# child_altium-designer.net
KiCad netlist of a schematic drawn in Altium Designer
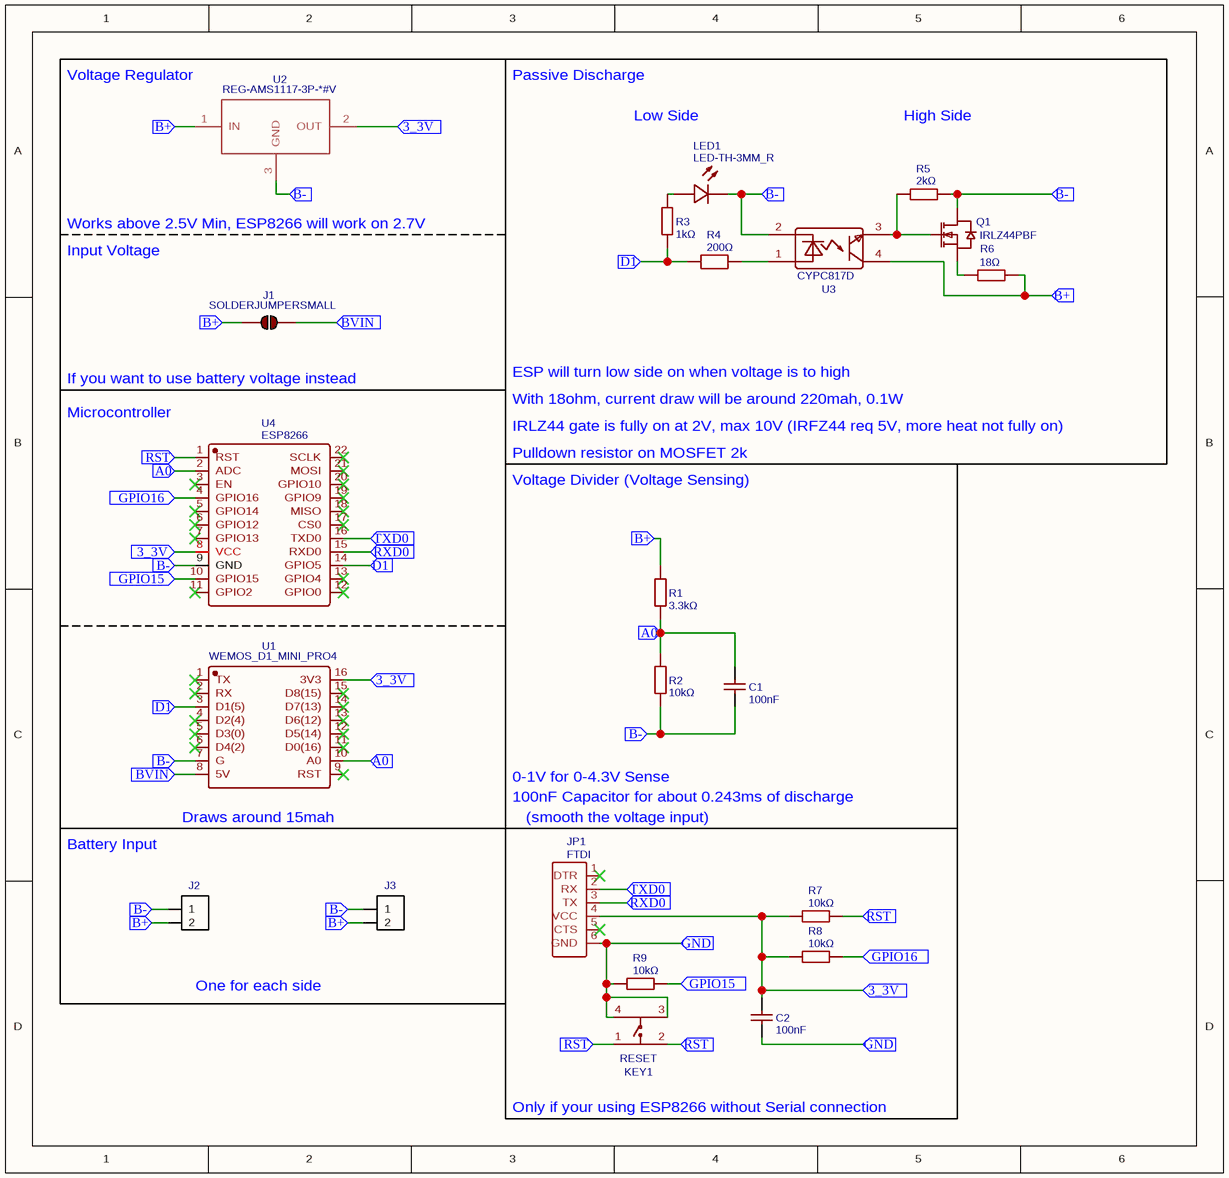
[diagram p0: child_altium-designer.schdoc]

(export (version "E")
  (design (tool "Eeschema 10.0.6"))
  (components
    (comp (ref "C1")
      (value "100nF")
      (fields
        (field (name "MANUFACTURER") "Kyocera AVX")
        (field (name "MANUFACTURER PART") "SR305C105KAR")
        (field (name "CONTRIBUTOR") "LCSC")
      )
      (libsource (lib "altium-import") (part "root_3_100nF_"))
    )
    (comp (ref "C2")
      (value "100nF")
      (fields
        (field (name "MANUFACTURER") "Kyocera AVX")
        (field (name "MANUFACTURER PART") "SR305C105KAR")
        (field (name "CONTRIBUTOR") "LCSC")
      )
      (libsource (lib "altium-import") (part "root_3_100nF_"))
    )
    (comp (ref "J1")
      (value "SOLDERJUMPERSMALL")
      (fields (field (name "CONTRIBUTOR") "stefan.klaeui"))
      (libsource (lib "altium-import") (part "root_0_SOLDERJUMPERSMALL_"))
    )
    (comp (ref "J2")
      (value "NO")
      (fields
        (field (name "MANUFACTURER") "BOOMELE")
        (field (name "MANUFACTURER PART") "Female headerHDR1X8-2.54")
        (field (name "CONTRIBUTOR") "Jacob KUNNATHOOR")
      )
      (libsource (lib "altium-import") (part "root_0_NO_"))
    )
    (comp (ref "J3")
      (value "NO")
      (fields
        (field (name "MANUFACTURER") "BOOMELE")
        (field (name "MANUFACTURER PART") "Female headerHDR1X8-2.54")
        (field (name "CONTRIBUTOR") "Jacob KUNNATHOOR")
      )
      (libsource (lib "altium-import") (part "root_0_NO_"))
    )
    (comp (ref "JP1")
      (value "FTDI")
      (fields (field (name "CONTRIBUTOR") "SparkFun"))
      (libsource (lib "altium-import") (part "root_0_FTDI_"))
    )
    (comp (ref "KEY1")
      (value "RESET")
      (fields (field (name "MANUFACTURER") "ReliaPro") (field (name "MANUFACTURER PART") "button6*6*8"))
      (libsource (lib "altium-import") (part "root_0_RESET_"))
    )
    (comp (ref "LED1")
      (value "LED-TH-3MM_R")
      (fields (field (name "MANUFACTURER PART") "LED-TH-3mm_R") (field (name "CONTRIBUTOR") "LCSC"))
      (libsource (lib "altium-import") (part "root_0_LED-TH-3MM_R_"))
    )
    (comp (ref "Q1")
      (value "IRLZ44PBF")
      (fields
        (field (name "MANUFACTURER") "VBsemi(微碧)")
        (field (name "MANUFACTURER PART") "IRLZ44PBF-VB")
        (field (name "CONTRIBUTOR") "LCSC")
      )
      (libsource (lib "altium-import") (part "root_0_IRLZ44PBF_"))
    )
    (comp (ref "R1")
      (value "3.3kΩ")
      (fields
        (field (name "MANUFACTURER") "YAGEO(国巨)")
        (field (name "MANUFACTURER PART") "MFR-25FTE52-33K")
        (field (name "CONTRIBUTOR") "LCSC")
      )
      (libsource (lib "altium-import") (part "root_3_3.3kΩ_"))
    )
    (comp (ref "R2")
      (value "10kΩ")
      (fields
        (field (name "MANUFACTURER") "YAGEO(国巨)")
        (field (name "MANUFACTURER PART") "MFR-25FTE52-100K")
        (field (name "CONTRIBUTOR") "LCSC")
      )
      (libsource (lib "altium-import") (part "root_3_10kΩ_"))
    )
    (comp (ref "R3")
      (value "1kΩ")
      (fields
        (field (name "MANUFACTURER") "YAGEO(国巨)")
        (field (name "MANUFACTURER PART") "MFR50SFTE52-1K")
        (field (name "CONTRIBUTOR") "LCSC")
      )
      (libsource (lib "altium-import") (part "root_1_1kΩ_"))
    )
    (comp (ref "R4")
      (value "200Ω")
      (fields
        (field (name "MANUFACTURER") "VO(翔胜)")
        (field (name "MANUFACTURER PART") "CR1/4W-200Ω±5%-ST52")
        (field (name "CONTRIBUTOR") "lcsc")
      )
      (libsource (lib "altium-import") (part "root_0_200Ω_"))
    )
    (comp (ref "R5")
      (value "2kΩ")
      (fields
        (field (name "MANUFACTURER") "YAGEO(国巨)")
        (field (name "MANUFACTURER PART") "MFR-25FTE52-2K")
        (field (name "CONTRIBUTOR") "LCSC")
      )
      (libsource (lib "altium-import") (part "root_0_2kΩ_"))
    )
    (comp (ref "R6")
      (value "18Ω")
      (fields
        (field (name "MANUFACTURER") "CCO(千志电子)")
        (field (name "MANUFACTURER PART") "CF1/4W-18Ω±5% T")
        (field (name "CONTRIBUTOR") "LCSC")
      )
      (libsource (lib "altium-import") (part "root_0_18Ω_"))
    )
    (comp (ref "R7")
      (value "10kΩ")
      (fields
        (field (name "MANUFACTURER") "YAGEO(国巨)")
        (field (name "MANUFACTURER PART") "MFR-25FTE52-33K")
        (field (name "CONTRIBUTOR") "LCSC")
      )
      (libsource (lib "altium-import") (part "root_2_10kΩ_"))
    )
    (comp (ref "R8")
      (value "10kΩ")
      (fields
        (field (name "MANUFACTURER") "YAGEO(国巨)")
        (field (name "MANUFACTURER PART") "MFR-25FTE52-33K")
        (field (name "CONTRIBUTOR") "LCSC")
      )
      (libsource (lib "altium-import") (part "root_2_10kΩ_"))
    )
    (comp (ref "R9")
      (value "10kΩ")
      (fields
        (field (name "MANUFACTURER") "YAGEO(国巨)")
        (field (name "MANUFACTURER PART") "MFR-25FTE52-33K")
        (field (name "CONTRIBUTOR") "LCSC")
      )
      (libsource (lib "altium-import") (part "root_2_10kΩ_"))
    )
    (comp (ref "U1")
      (value "WEMOS_D1_MINI_PRO4")
      (fields (field (name "MANUFACTURER PART") "Wemos_D1_mini_Pro4") (field (name "CONTRIBUTOR") "LCSC"))
      (libsource (lib "altium-import") (part "root_0_WEMOS_D1_MINI_PRO4_"))
    )
    (comp (ref "U2")
      (value "REG-AMS1117-3P-*#V")
      (fields (field (name "CONTRIBUTOR") "jboutin"))
      (libsource (lib "altium-import") (part "root_0_REG-AMS1117-3P-*#V_"))
    )
    (comp (ref "U3")
      (value "CYPC817D")
      (fields (field (name "MANUFACTURER") "OCIC(卓睿科)") (field (name "CONTRIBUTOR") "lcsc"))
      (libsource (lib "altium-import") (part "root_0_CYPC817D_"))
    )
    (comp (ref "U4")
      (value "ESP8266")
      (fields (field (name "CONTRIBUTOR") "LCSC"))
      (libsource (lib "altium-import") (part "root_0_ESP8266_"))
    )
  )
  (nets
    (net (code "1") (name "/3_3V") (class "Default")
      (node (ref "C2") (pin "1") (pinfunction "1_1") (pintype "passive"))
      (node (ref "JP1") (pin "4") (pinfunction "VCC_4") (pintype "passive"))
      (node (ref "R7") (pin "2") (pinfunction "2_2") (pintype "passive"))
      (node (ref "R8") (pin "2") (pinfunction "2_2") (pintype "passive"))
      (node (ref "U1") (pin "16") (pinfunction "3V3_16") (pintype "passive"))
      (node (ref "U2") (pin "2") (pinfunction "OUT_2") (pintype "passive"))
      (node (ref "U4") (pin "8") (pinfunction "VCC_8") (pintype "passive"))
    )
    (net (code "2") (name "/A0") (class "Default")
      (node (ref "C1") (pin "1") (pinfunction "1_1") (pintype "passive"))
      (node (ref "R1") (pin "2") (pinfunction "2_2") (pintype "passive"))
      (node (ref "R2") (pin "1") (pinfunction "1_1") (pintype "passive"))
      (node (ref "U1") (pin "10") (pinfunction "A0_10") (pintype "passive"))
      (node (ref "U4") (pin "2") (pinfunction "ADC_2") (pintype "passive"))
    )
    (net (code "3") (name "/B+") (class "Default")
      (node (ref "J1") (pin "1") (pinfunction "1_1") (pintype "passive"))
      (node (ref "J2") (pin "2") (pinfunction "2_2") (pintype "passive"))
      (node (ref "J3") (pin "2") (pinfunction "2_2") (pintype "passive"))
      (node (ref "R1") (pin "1") (pinfunction "1_1") (pintype "passive"))
      (node (ref "R6") (pin "2") (pinfunction "2_2") (pintype "passive"))
      (node (ref "U2") (pin "1") (pinfunction "IN_1") (pintype "passive"))
      (node (ref "U3") (pin "4") (pinfunction "COL_4") (pintype "passive"))
    )
    (net (code "4") (name "/B-") (class "Default")
      (node (ref "C1") (pin "2") (pinfunction "2_2") (pintype "passive"))
      (node (ref "J2") (pin "1") (pinfunction "1_1") (pintype "passive"))
      (node (ref "J3") (pin "1") (pinfunction "1_1") (pintype "passive"))
      (node (ref "LED1") (pin "2") (pinfunction "2_2") (pintype "passive"))
      (node (ref "Q1") (pin "2") (pinfunction "D_2") (pintype "passive"))
      (node (ref "R2") (pin "2") (pinfunction "2_2") (pintype "passive"))
      (node (ref "R5") (pin "2") (pinfunction "2_2") (pintype "passive"))
      (node (ref "U1") (pin "7") (pinfunction "G_7") (pintype "passive"))
      (node (ref "U2") (pin "3") (pinfunction "GND_3") (pintype "passive"))
      (node (ref "U3") (pin "2") (pinfunction "CAT_2") (pintype "passive"))
      (node (ref "U4") (pin "9") (pinfunction "GND_9") (pintype "passive"))
    )
    (net (code "5") (name "/BVIN") (class "Default")
      (node (ref "J1") (pin "2") (pinfunction "2_2") (pintype "passive"))
      (node (ref "U1") (pin "8") (pinfunction "5V_8") (pintype "passive"))
    )
    (net (code "6") (name "/D1") (class "Default")
      (node (ref "R3") (pin "1") (pinfunction "1_1") (pintype "passive"))
      (node (ref "R4") (pin "1") (pinfunction "1_1") (pintype "passive"))
      (node (ref "U1") (pin "3") (pinfunction "D1(5)_3") (pintype "passive"))
      (node (ref "U4") (pin "14") (pinfunction "GPIO5_14") (pintype "passive"))
    )
    (net (code "7") (name "/GND") (class "Default")
      (node (ref "C2") (pin "2") (pinfunction "2_2") (pintype "passive"))
      (node (ref "JP1") (pin "6") (pinfunction "GND_6") (pintype "passive"))
      (node (ref "KEY1") (pin "3") (pinfunction "3_3") (pintype "passive"))
      (node (ref "KEY1") (pin "4") (pinfunction "4_4") (pintype "passive"))
      (node (ref "R9") (pin "2") (pinfunction "2_2") (pintype "passive"))
    )
    (net (code "8") (name "/GPIO15") (class "Default")
      (node (ref "R9") (pin "1") (pinfunction "1_1") (pintype "passive"))
      (node (ref "U4") (pin "10") (pinfunction "GPIO15_10") (pintype "passive"))
    )
    (net (code "9") (name "/GPIO16") (class "Default")
      (node (ref "R8") (pin "1") (pinfunction "1_1") (pintype "passive"))
      (node (ref "U4") (pin "4") (pinfunction "GPIO16_4") (pintype "passive"))
    )
    (net (code "10") (name "/RST") (class "Default")
      (node (ref "KEY1") (pin "1") (pinfunction "1_1") (pintype "passive"))
      (node (ref "KEY1") (pin "2") (pinfunction "2_2") (pintype "passive"))
      (node (ref "R7") (pin "1") (pinfunction "1_1") (pintype "passive"))
      (node (ref "U4") (pin "1") (pinfunction "RST_1") (pintype "passive"))
    )
    (net (code "11") (name "/RXD0") (class "Default")
      (node (ref "JP1") (pin "3") (pinfunction "TX_3") (pintype "passive"))
      (node (ref "U4") (pin "15") (pinfunction "RXD0_15") (pintype "passive"))
    )
    (net (code "12") (name "/TXD0") (class "Default")
      (node (ref "JP1") (pin "2") (pinfunction "RX_2") (pintype "passive"))
      (node (ref "U4") (pin "16") (pinfunction "TXD0_16") (pintype "passive"))
    )
    (net (code "13") (name "Net-(LED1-Pad1)") (class "Default")
      (node (ref "LED1") (pin "1") (pinfunction "1_1") (pintype "passive"))
      (node (ref "R3") (pin "2") (pinfunction "2_2") (pintype "passive"))
    )
    (net (code "14") (name "Net-(Q1-G)") (class "Default")
      (node (ref "Q1") (pin "1") (pinfunction "G_1") (pintype "passive"))
      (node (ref "R5") (pin "1") (pinfunction "1_1") (pintype "passive"))
      (node (ref "U3") (pin "3") (pinfunction "EM_3") (pintype "passive"))
    )
    (net (code "15") (name "Net-(Q1-S)") (class "Default")
      (node (ref "Q1") (pin "3") (pinfunction "S_3") (pintype "passive"))
      (node (ref "R6") (pin "1") (pinfunction "1_1") (pintype "passive"))
    )
    (net (code "16") (name "Net-(U3-AN)") (class "Default")
      (node (ref "R4") (pin "2") (pinfunction "2_2") (pintype "passive"))
      (node (ref "U3") (pin "1") (pinfunction "AN_1") (pintype "passive"))
    )
    (net (code "17") (name "unconnected-(JP1-CTS-Pad5)") (class "Default")
      (node (ref "JP1") (pin "5") (pinfunction "CTS_5") (pintype "passive+no_connect"))
    )
    (net (code "18") (name "unconnected-(JP1-DTR-Pad1)") (class "Default")
      (node (ref "JP1") (pin "1") (pinfunction "DTR_1") (pintype "passive+no_connect"))
    )
    (net (code "19") (name "unconnected-(U1-D0(16)-Pad11)") (class "Default")
      (node (ref "U1") (pin "11") (pinfunction "D0(16)_11") (pintype "passive+no_connect"))
    )
    (net (code "20") (name "unconnected-(U1-D2(4)-Pad4)") (class "Default")
      (node (ref "U1") (pin "4") (pinfunction "D2(4)_4") (pintype "passive+no_connect"))
    )
    (net (code "21") (name "unconnected-(U1-D3(0)-Pad5)") (class "Default")
      (node (ref "U1") (pin "5") (pinfunction "D3(0)_5") (pintype "passive+no_connect"))
    )
    (net (code "22") (name "unconnected-(U1-D4(2)-Pad6)") (class "Default")
      (node (ref "U1") (pin "6") (pinfunction "D4(2)_6") (pintype "passive+no_connect"))
    )
    (net (code "23") (name "unconnected-(U1-D5(14)-Pad12)") (class "Default")
      (node (ref "U1") (pin "12") (pinfunction "D5(14)_12") (pintype "passive+no_connect"))
    )
    (net (code "24") (name "unconnected-(U1-D6(12)-Pad13)") (class "Default")
      (node (ref "U1") (pin "13") (pinfunction "D6(12)_13") (pintype "passive+no_connect"))
    )
    (net (code "25") (name "unconnected-(U1-D7(13)-Pad14)") (class "Default")
      (node (ref "U1") (pin "14") (pinfunction "D7(13)_14") (pintype "passive+no_connect"))
    )
    (net (code "26") (name "unconnected-(U1-D8(15)-Pad15)") (class "Default")
      (node (ref "U1") (pin "15") (pinfunction "D8(15)_15") (pintype "passive+no_connect"))
    )
    (net (code "27") (name "unconnected-(U1-RST-Pad9)") (class "Default")
      (node (ref "U1") (pin "9") (pinfunction "RST_9") (pintype "passive+no_connect"))
    )
    (net (code "28") (name "unconnected-(U1-RX-Pad2)") (class "Default")
      (node (ref "U1") (pin "2") (pinfunction "RX_2") (pintype "passive+no_connect"))
    )
    (net (code "29") (name "unconnected-(U1-TX-Pad1)") (class "Default")
      (node (ref "U1") (pin "1") (pinfunction "TX_1") (pintype "passive+no_connect"))
    )
    (net (code "30") (name "unconnected-(U4-CS0-Pad17)") (class "Default")
      (node (ref "U4") (pin "17") (pinfunction "CS0_17") (pintype "passive+no_connect"))
    )
    (net (code "31") (name "unconnected-(U4-EN-Pad3)") (class "Default")
      (node (ref "U4") (pin "3") (pinfunction "EN_3") (pintype "passive+no_connect"))
    )
    (net (code "32") (name "unconnected-(U4-GPIO0-Pad12)") (class "Default")
      (node (ref "U4") (pin "12") (pinfunction "GPIO0_12") (pintype "passive+no_connect"))
    )
    (net (code "33") (name "unconnected-(U4-GPIO2-Pad11)") (class "Default")
      (node (ref "U4") (pin "11") (pinfunction "GPIO2_11") (pintype "passive+no_connect"))
    )
    (net (code "34") (name "unconnected-(U4-GPIO4-Pad13)") (class "Default")
      (node (ref "U4") (pin "13") (pinfunction "GPIO4_13") (pintype "passive+no_connect"))
    )
    (net (code "35") (name "unconnected-(U4-GPIO9-Pad19)") (class "Default")
      (node (ref "U4") (pin "19") (pinfunction "GPIO9_19") (pintype "passive+no_connect"))
    )
    (net (code "36") (name "unconnected-(U4-GPIO10-Pad20)") (class "Default")
      (node (ref "U4") (pin "20") (pinfunction "GPIO10_20") (pintype "passive+no_connect"))
    )
    (net (code "37") (name "unconnected-(U4-GPIO12-Pad6)") (class "Default")
      (node (ref "U4") (pin "6") (pinfunction "GPIO12_6") (pintype "passive+no_connect"))
    )
    (net (code "38") (name "unconnected-(U4-GPIO13-Pad7)") (class "Default")
      (node (ref "U4") (pin "7") (pinfunction "GPIO13_7") (pintype "passive+no_connect"))
    )
    (net (code "39") (name "unconnected-(U4-GPIO14-Pad5)") (class "Default")
      (node (ref "U4") (pin "5") (pinfunction "GPIO14_5") (pintype "passive+no_connect"))
    )
    (net (code "40") (name "unconnected-(U4-MISO-Pad18)") (class "Default")
      (node (ref "U4") (pin "18") (pinfunction "MISO_18") (pintype "passive+no_connect"))
    )
    (net (code "41") (name "unconnected-(U4-MOSI-Pad21)") (class "Default")
      (node (ref "U4") (pin "21") (pinfunction "MOSI_21") (pintype "passive+no_connect"))
    )
    (net (code "42") (name "unconnected-(U4-SCLK-Pad22)") (class "Default")
      (node (ref "U4") (pin "22") (pinfunction "SCLK_22") (pintype "passive+no_connect"))
    )
  )
)
